# 7segroganti.net
KiCad netlist of a schematic drawn in EAGLE
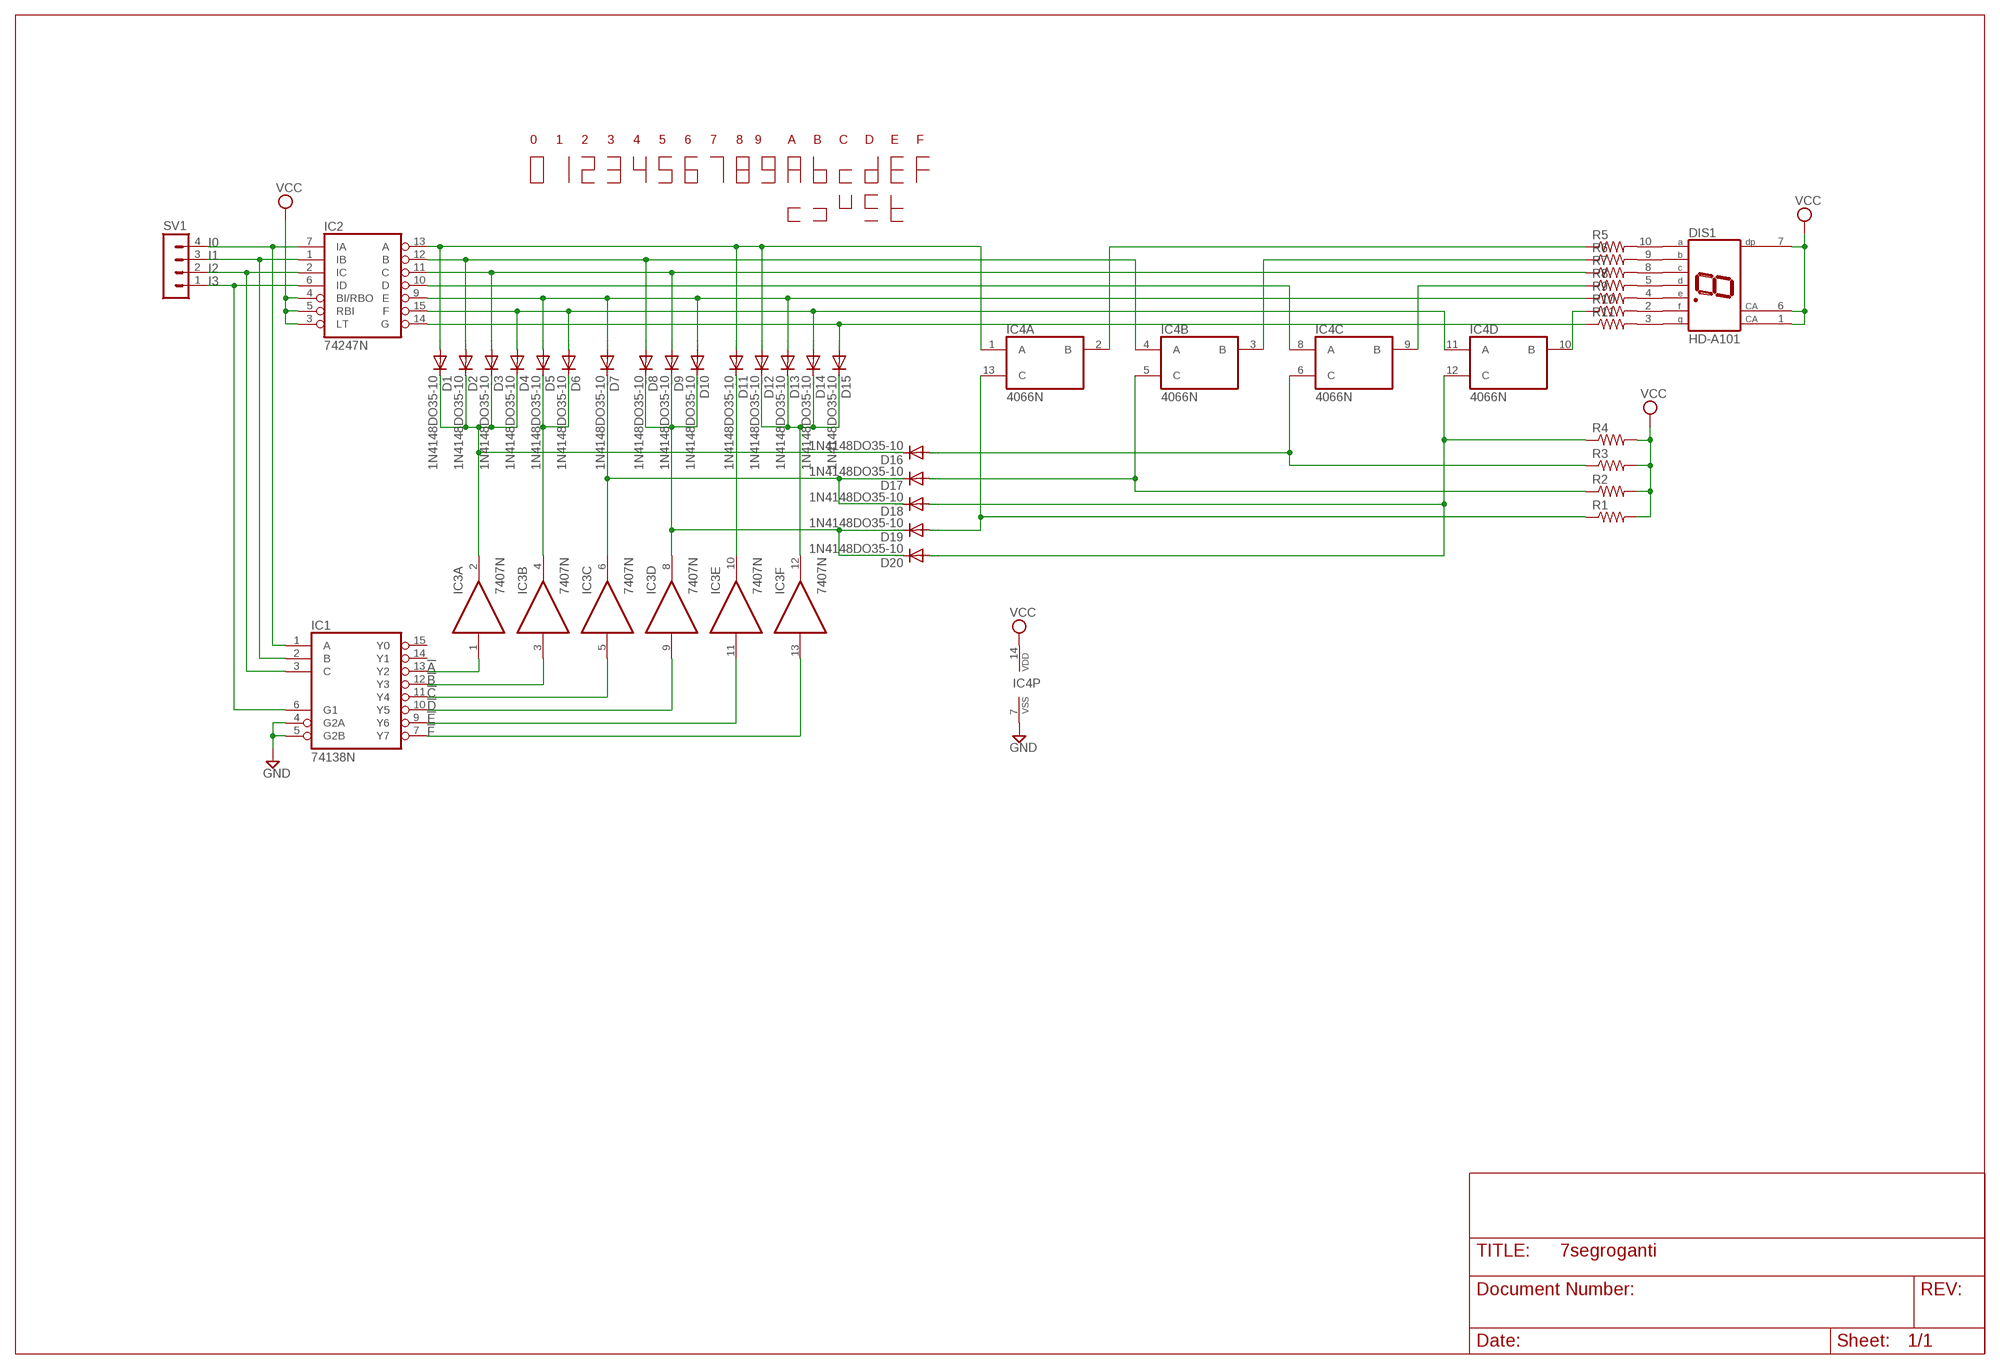
[diagram p0: schematic, sheet 1]

(export (version "E")
  (design (tool "Eeschema 10.0.6"))
  (components
    (comp (ref "D1")
      (value "1N4148DO35-10")
      (footprint "eagle-import:DO35-10")
      (libsource (lib "eagle-import") (part "1N4148DO35-10"))
    )
    (comp (ref "D2")
      (value "1N4148DO35-10")
      (footprint "eagle-import:DO35-10")
      (libsource (lib "eagle-import") (part "1N4148DO35-10"))
    )
    (comp (ref "D3")
      (value "1N4148DO35-10")
      (footprint "eagle-import:DO35-10")
      (libsource (lib "eagle-import") (part "1N4148DO35-10"))
    )
    (comp (ref "D4")
      (value "1N4148DO35-10")
      (footprint "eagle-import:DO35-10")
      (libsource (lib "eagle-import") (part "1N4148DO35-10"))
    )
    (comp (ref "D5")
      (value "1N4148DO35-10")
      (footprint "eagle-import:DO35-10")
      (libsource (lib "eagle-import") (part "1N4148DO35-10"))
    )
    (comp (ref "D6")
      (value "1N4148DO35-10")
      (footprint "eagle-import:DO35-10")
      (libsource (lib "eagle-import") (part "1N4148DO35-10"))
    )
    (comp (ref "D7")
      (value "1N4148DO35-10")
      (footprint "eagle-import:DO35-10")
      (libsource (lib "eagle-import") (part "1N4148DO35-10"))
    )
    (comp (ref "D8")
      (value "1N4148DO35-10")
      (footprint "eagle-import:DO35-10")
      (libsource (lib "eagle-import") (part "1N4148DO35-10"))
    )
    (comp (ref "D9")
      (value "1N4148DO35-10")
      (footprint "eagle-import:DO35-10")
      (libsource (lib "eagle-import") (part "1N4148DO35-10"))
    )
    (comp (ref "D10")
      (value "1N4148DO35-10")
      (footprint "eagle-import:DO35-10")
      (libsource (lib "eagle-import") (part "1N4148DO35-10"))
    )
    (comp (ref "D11")
      (value "1N4148DO35-10")
      (footprint "eagle-import:DO35-10")
      (libsource (lib "eagle-import") (part "1N4148DO35-10"))
    )
    (comp (ref "D12")
      (value "1N4148DO35-10")
      (footprint "eagle-import:DO35-10")
      (libsource (lib "eagle-import") (part "1N4148DO35-10"))
    )
    (comp (ref "D13")
      (value "1N4148DO35-10")
      (footprint "eagle-import:DO35-10")
      (libsource (lib "eagle-import") (part "1N4148DO35-10"))
    )
    (comp (ref "D14")
      (value "1N4148DO35-10")
      (footprint "eagle-import:DO35-10")
      (libsource (lib "eagle-import") (part "1N4148DO35-10"))
    )
    (comp (ref "D15")
      (value "1N4148DO35-10")
      (footprint "eagle-import:DO35-10")
      (libsource (lib "eagle-import") (part "1N4148DO35-10"))
    )
    (comp (ref "D16")
      (value "1N4148DO35-10")
      (footprint "eagle-import:DO35-10")
      (libsource (lib "eagle-import") (part "1N4148DO35-10"))
    )
    (comp (ref "D17")
      (value "1N4148DO35-10")
      (footprint "eagle-import:DO35-10")
      (libsource (lib "eagle-import") (part "1N4148DO35-10"))
    )
    (comp (ref "D18")
      (value "1N4148DO35-10")
      (footprint "eagle-import:DO35-10")
      (libsource (lib "eagle-import") (part "1N4148DO35-10"))
    )
    (comp (ref "D19")
      (value "1N4148DO35-10")
      (footprint "eagle-import:DO35-10")
      (libsource (lib "eagle-import") (part "1N4148DO35-10"))
    )
    (comp (ref "D20")
      (value "1N4148DO35-10")
      (footprint "eagle-import:DO35-10")
      (libsource (lib "eagle-import") (part "1N4148DO35-10"))
    )
    (comp (ref "DIS1")
      (value "HD-A101")
      (footprint "eagle-import:HDSP-A")
      (libsource (lib "eagle-import") (part "HD-A101"))
    )
    (comp (ref "IC1")
      (value "74138N")
      (footprint "eagle-import:DIL16")
      (libsource (lib "eagle-import") (part "74138NS"))
    )
    (comp (ref "IC2")
      (value "74247N")
      (footprint "eagle-import:DIL16")
      (libsource (lib "eagle-import") (part "7446N"))
    )
    (comp (ref "IC3")
      (value "7407N")
      (footprint "eagle-import:DIL14")
      (libsource (lib "eagle-import") (part "7407N"))
    )
    (comp (ref "IC4")
      (value "4066N")
      (footprint "eagle-import:DIL14")
      (libsource (lib "eagle-import") (part "4066N"))
    )
    (comp (ref "R1")
      (value "R-US_0207/10")
      (footprint "eagle-import:0207_10")
      (libsource (lib "eagle-import") (part "R-US_0207/10"))
    )
    (comp (ref "R2")
      (value "R-US_0207/10")
      (footprint "eagle-import:0207_10")
      (libsource (lib "eagle-import") (part "R-US_0207/10"))
    )
    (comp (ref "R3")
      (value "R-US_0207/10")
      (footprint "eagle-import:0207_10")
      (libsource (lib "eagle-import") (part "R-US_0207/10"))
    )
    (comp (ref "R4")
      (value "R-US_0207/10")
      (footprint "eagle-import:0207_10")
      (libsource (lib "eagle-import") (part "R-US_0207/10"))
    )
    (comp (ref "R5")
      (value "R-US_0207/10")
      (footprint "eagle-import:0207_10")
      (libsource (lib "eagle-import") (part "R-US_0207/10"))
    )
    (comp (ref "R6")
      (value "R-US_0207/10")
      (footprint "eagle-import:0207_10")
      (libsource (lib "eagle-import") (part "R-US_0207/10"))
    )
    (comp (ref "R7")
      (value "R-US_0207/10")
      (footprint "eagle-import:0207_10")
      (libsource (lib "eagle-import") (part "R-US_0207/10"))
    )
    (comp (ref "R8")
      (value "R-US_0207/10")
      (footprint "eagle-import:0207_10")
      (libsource (lib "eagle-import") (part "R-US_0207/10"))
    )
    (comp (ref "R9")
      (value "R-US_0207/10")
      (footprint "eagle-import:0207_10")
      (libsource (lib "eagle-import") (part "R-US_0207/10"))
    )
    (comp (ref "R10")
      (value "R-US_0207/10")
      (footprint "eagle-import:0207_10")
      (libsource (lib "eagle-import") (part "R-US_0207/10"))
    )
    (comp (ref "R11")
      (value "R-US_0207/10")
      (footprint "eagle-import:0207_10")
      (libsource (lib "eagle-import") (part "R-US_0207/10"))
    )
    (comp (ref "SV1")
      (value "MA04-1")
      (footprint "eagle-import:MA04-1")
      (libsource (lib "eagle-import") (part "MA04-1"))
    )
  )
  (nets
    (net (code "1") (name "/I0") (class "Default")
      (node (ref "IC1") (pin "1") (pinfunction "A_1") (pintype "input"))
      (node (ref "IC2") (pin "7") (pinfunction "IA_7") (pintype "input"))
      (node (ref "SV1") (pin "4") (pinfunction "4_4") (pintype "passive"))
    )
    (net (code "2") (name "/I1") (class "Default")
      (node (ref "IC1") (pin "2") (pinfunction "B_2") (pintype "input"))
      (node (ref "IC2") (pin "1") (pinfunction "IB_1") (pintype "input"))
      (node (ref "SV1") (pin "3") (pinfunction "3_3") (pintype "passive"))
    )
    (net (code "3") (name "/I2") (class "Default")
      (node (ref "IC1") (pin "3") (pinfunction "C_3") (pintype "input"))
      (node (ref "IC2") (pin "2") (pinfunction "IC_2") (pintype "input"))
      (node (ref "SV1") (pin "2") (pinfunction "2_2") (pintype "passive"))
    )
    (net (code "4") (name "/I3") (class "Default")
      (node (ref "IC1") (pin "6") (pinfunction "G1_6") (pintype "input"))
      (node (ref "IC2") (pin "6") (pinfunction "ID_6") (pintype "input"))
      (node (ref "SV1") (pin "1") (pinfunction "1_1") (pintype "passive"))
    )
    (net (code "5") (name "/~{A}") (class "Default")
      (node (ref "IC1") (pin "13") (pinfunction "Y2_13") (pintype "output"))
      (node (ref "IC3") (pin "1") (pinfunction "I_1") (pintype "input"))
    )
    (net (code "6") (name "/~{B}") (class "Default")
      (node (ref "IC1") (pin "12") (pinfunction "Y3_12") (pintype "output"))
      (node (ref "IC3") (pin "3") (pinfunction "I_3") (pintype "input"))
    )
    (net (code "7") (name "/~{C}") (class "Default")
      (node (ref "IC1") (pin "11") (pinfunction "Y4_11") (pintype "output"))
      (node (ref "IC3") (pin "5") (pinfunction "I_5") (pintype "input"))
    )
    (net (code "8") (name "/~{D}") (class "Default")
      (node (ref "IC1") (pin "10") (pinfunction "Y5_10") (pintype "output"))
      (node (ref "IC3") (pin "9") (pinfunction "I_9") (pintype "input"))
    )
    (net (code "9") (name "/~{E}") (class "Default")
      (node (ref "IC1") (pin "9") (pinfunction "Y6_9") (pintype "output"))
      (node (ref "IC3") (pin "11") (pinfunction "I_11") (pintype "input"))
    )
    (net (code "10") (name "/~{F}") (class "Default")
      (node (ref "IC1") (pin "7") (pinfunction "Y7_7") (pintype "output"))
      (node (ref "IC3") (pin "13") (pinfunction "I_13") (pintype "input"))
    )
    (net (code "11") (name "GND") (class "Default")
      (node (ref "IC1") (pin "4") (pinfunction "G2A_4") (pintype "input"))
      (node (ref "IC1") (pin "5") (pinfunction "G2B_5") (pintype "input"))
      (node (ref "IC4") (pin "7") (pinfunction "VSS_7") (pintype "power_in"))
    )
    (net (code "12") (name "Net-(DIS1-A)") (class "Default")
      (node (ref "DIS1") (pin "10") (pinfunction "A_10") (pintype "passive"))
      (node (ref "R5") (pin "2") (pinfunction "2_2") (pintype "passive"))
    )
    (net (code "13") (name "Net-(DIS1-B)") (class "Default")
      (node (ref "DIS1") (pin "9") (pinfunction "B_9") (pintype "passive"))
      (node (ref "R6") (pin "2") (pinfunction "2_2") (pintype "passive"))
    )
    (net (code "14") (name "Net-(DIS1-C)") (class "Default")
      (node (ref "DIS1") (pin "8") (pinfunction "C_8") (pintype "passive"))
      (node (ref "R7") (pin "2") (pinfunction "2_2") (pintype "passive"))
    )
    (net (code "15") (name "Net-(DIS1-D)") (class "Default")
      (node (ref "DIS1") (pin "5") (pinfunction "D_5") (pintype "passive"))
      (node (ref "R8") (pin "2") (pinfunction "2_2") (pintype "passive"))
    )
    (net (code "16") (name "Net-(DIS1-E)") (class "Default")
      (node (ref "DIS1") (pin "4") (pinfunction "E_4") (pintype "passive"))
      (node (ref "R9") (pin "2") (pinfunction "2_2") (pintype "passive"))
    )
    (net (code "17") (name "Net-(DIS1-F)") (class "Default")
      (node (ref "DIS1") (pin "2") (pinfunction "F_2") (pintype "passive"))
      (node (ref "R10") (pin "2") (pinfunction "2_2") (pintype "passive"))
    )
    (net (code "18") (name "Net-(DIS1-G)") (class "Default")
      (node (ref "DIS1") (pin "3") (pinfunction "G_3") (pintype "passive"))
      (node (ref "R11") (pin "2") (pinfunction "2_2") (pintype "passive"))
    )
    (net (code "19") (name "Net-(IC2A-A)") (class "Default")
      (node (ref "D1") (pin "A") (pinfunction "A_A") (pintype "passive"))
      (node (ref "D11") (pin "A") (pinfunction "A_A") (pintype "passive"))
      (node (ref "D12") (pin "A") (pinfunction "A_A") (pintype "passive"))
      (node (ref "IC2") (pin "13") (pinfunction "A_13") (pintype "open_collector"))
      (node (ref "IC4") (pin "1") (pinfunction "A_1") (pintype "tri_state"))
    )
    (net (code "20") (name "Net-(IC2A-B)") (class "Default")
      (node (ref "D2") (pin "A") (pinfunction "A_A") (pintype "passive"))
      (node (ref "D8") (pin "A") (pinfunction "A_A") (pintype "passive"))
      (node (ref "IC2") (pin "12") (pinfunction "B_12") (pintype "open_collector"))
      (node (ref "IC4") (pin "4") (pinfunction "A_4") (pintype "tri_state"))
    )
    (net (code "21") (name "Net-(IC2A-C)") (class "Default")
      (node (ref "D3") (pin "A") (pinfunction "A_A") (pintype "passive"))
      (node (ref "D9") (pin "A") (pinfunction "A_A") (pintype "passive"))
      (node (ref "IC2") (pin "11") (pinfunction "C_11") (pintype "open_collector"))
      (node (ref "R7") (pin "1") (pinfunction "1_1") (pintype "passive"))
    )
    (net (code "22") (name "Net-(IC2A-D)") (class "Default")
      (node (ref "IC2") (pin "10") (pinfunction "D_10") (pintype "open_collector"))
      (node (ref "IC4") (pin "8") (pinfunction "A_8") (pintype "tri_state"))
    )
    (net (code "23") (name "Net-(IC2A-E)") (class "Default")
      (node (ref "D10") (pin "A") (pinfunction "A_A") (pintype "passive"))
      (node (ref "D13") (pin "A") (pinfunction "A_A") (pintype "passive"))
      (node (ref "D5") (pin "A") (pinfunction "A_A") (pintype "passive"))
      (node (ref "D7") (pin "A") (pinfunction "A_A") (pintype "passive"))
      (node (ref "IC2") (pin "9") (pinfunction "E_9") (pintype "open_collector"))
      (node (ref "R9") (pin "1") (pinfunction "1_1") (pintype "passive"))
    )
    (net (code "24") (name "Net-(IC2A-F)") (class "Default")
      (node (ref "D14") (pin "A") (pinfunction "A_A") (pintype "passive"))
      (node (ref "D4") (pin "A") (pinfunction "A_A") (pintype "passive"))
      (node (ref "D6") (pin "A") (pinfunction "A_A") (pintype "passive"))
      (node (ref "IC2") (pin "15") (pinfunction "F_15") (pintype "open_collector"))
      (node (ref "IC4") (pin "11") (pinfunction "A_11") (pintype "tri_state"))
    )
    (net (code "25") (name "Net-(IC2A-G)") (class "Default")
      (node (ref "D15") (pin "A") (pinfunction "A_A") (pintype "passive"))
      (node (ref "IC2") (pin "14") (pinfunction "G_14") (pintype "open_collector"))
      (node (ref "R11") (pin "1") (pinfunction "1_1") (pintype "passive"))
    )
    (net (code "26") (name "Net-(IC3A-O)") (class "Default")
      (node (ref "D1") (pin "C") (pinfunction "C_C") (pintype "passive"))
      (node (ref "D16") (pin "C") (pinfunction "C_C") (pintype "passive"))
      (node (ref "D2") (pin "C") (pinfunction "C_C") (pintype "passive"))
      (node (ref "D3") (pin "C") (pinfunction "C_C") (pintype "passive"))
      (node (ref "D4") (pin "C") (pinfunction "C_C") (pintype "passive"))
      (node (ref "IC3") (pin "2") (pinfunction "O_2") (pintype "open_collector"))
    )
    (net (code "27") (name "Net-(IC3B-O)") (class "Default")
      (node (ref "D5") (pin "C") (pinfunction "C_C") (pintype "passive"))
      (node (ref "D6") (pin "C") (pinfunction "C_C") (pintype "passive"))
      (node (ref "IC3") (pin "4") (pinfunction "O_4") (pintype "open_collector"))
    )
    (net (code "28") (name "Net-(IC3C-O)") (class "Default")
      (node (ref "D17") (pin "C") (pinfunction "C_C") (pintype "passive"))
      (node (ref "D18") (pin "C") (pinfunction "C_C") (pintype "passive"))
      (node (ref "D7") (pin "C") (pinfunction "C_C") (pintype "passive"))
      (node (ref "IC3") (pin "6") (pinfunction "O_6") (pintype "open_collector"))
    )
    (net (code "29") (name "Net-(IC3D-O)") (class "Default")
      (node (ref "D10") (pin "C") (pinfunction "C_C") (pintype "passive"))
      (node (ref "D19") (pin "C") (pinfunction "C_C") (pintype "passive"))
      (node (ref "D20") (pin "C") (pinfunction "C_C") (pintype "passive"))
      (node (ref "D8") (pin "C") (pinfunction "C_C") (pintype "passive"))
      (node (ref "D9") (pin "C") (pinfunction "C_C") (pintype "passive"))
      (node (ref "IC3") (pin "8") (pinfunction "O_8") (pintype "open_collector"))
    )
    (net (code "30") (name "Net-(IC3E-O)") (class "Default")
      (node (ref "D11") (pin "C") (pinfunction "C_C") (pintype "passive"))
      (node (ref "IC3") (pin "10") (pinfunction "O_10") (pintype "open_collector"))
    )
    (net (code "31") (name "Net-(IC3F-O)") (class "Default")
      (node (ref "D12") (pin "C") (pinfunction "C_C") (pintype "passive"))
      (node (ref "D13") (pin "C") (pinfunction "C_C") (pintype "passive"))
      (node (ref "D14") (pin "C") (pinfunction "C_C") (pintype "passive"))
      (node (ref "D15") (pin "C") (pinfunction "C_C") (pintype "passive"))
      (node (ref "IC3") (pin "12") (pinfunction "O_12") (pintype "open_collector"))
    )
    (net (code "32") (name "Net-(IC4A-B)") (class "Default")
      (node (ref "IC4") (pin "2") (pinfunction "B_2") (pintype "tri_state"))
      (node (ref "R5") (pin "1") (pinfunction "1_1") (pintype "passive"))
    )
    (net (code "33") (name "Net-(IC4A-C)") (class "Default")
      (node (ref "D19") (pin "A") (pinfunction "A_A") (pintype "passive"))
      (node (ref "IC4") (pin "13") (pinfunction "C_13") (pintype "input"))
      (node (ref "R1") (pin "1") (pinfunction "1_1") (pintype "passive"))
    )
    (net (code "34") (name "Net-(IC4B-B)") (class "Default")
      (node (ref "IC4") (pin "3") (pinfunction "B_3") (pintype "tri_state"))
      (node (ref "R6") (pin "1") (pinfunction "1_1") (pintype "passive"))
    )
    (net (code "35") (name "Net-(IC4B-C)") (class "Default")
      (node (ref "D17") (pin "A") (pinfunction "A_A") (pintype "passive"))
      (node (ref "IC4") (pin "5") (pinfunction "C_5") (pintype "input"))
      (node (ref "R2") (pin "1") (pinfunction "1_1") (pintype "passive"))
    )
    (net (code "36") (name "Net-(IC4C-B)") (class "Default")
      (node (ref "IC4") (pin "9") (pinfunction "B_9") (pintype "tri_state"))
      (node (ref "R8") (pin "1") (pinfunction "1_1") (pintype "passive"))
    )
    (net (code "37") (name "Net-(IC4C-C)") (class "Default")
      (node (ref "D16") (pin "A") (pinfunction "A_A") (pintype "passive"))
      (node (ref "IC4") (pin "6") (pinfunction "C_6") (pintype "input"))
      (node (ref "R3") (pin "1") (pinfunction "1_1") (pintype "passive"))
    )
    (net (code "38") (name "Net-(IC4D-B)") (class "Default")
      (node (ref "IC4") (pin "10") (pinfunction "B_10") (pintype "tri_state"))
      (node (ref "R10") (pin "1") (pinfunction "1_1") (pintype "passive"))
    )
    (net (code "39") (name "Net-(IC4D-C)") (class "Default")
      (node (ref "D18") (pin "A") (pinfunction "A_A") (pintype "passive"))
      (node (ref "D20") (pin "A") (pinfunction "A_A") (pintype "passive"))
      (node (ref "IC4") (pin "12") (pinfunction "C_12") (pintype "input"))
      (node (ref "R4") (pin "1") (pinfunction "1_1") (pintype "passive"))
    )
    (net (code "40") (name "VCC") (class "Default")
      (node (ref "DIS1") (pin "1") (pinfunction "CA_1") (pintype "passive"))
      (node (ref "DIS1") (pin "6") (pinfunction "CA_6") (pintype "passive"))
      (node (ref "DIS1") (pin "7") (pinfunction "DP_7") (pintype "passive"))
      (node (ref "IC2") (pin "3") (pinfunction "LT_3") (pintype "input"))
      (node (ref "IC2") (pin "4") (pinfunction "BI/RBO_4") (pintype "input"))
      (node (ref "IC2") (pin "5") (pinfunction "RBI_5") (pintype "input"))
      (node (ref "IC4") (pin "14") (pinfunction "VDD_14") (pintype "power_in"))
      (node (ref "R1") (pin "2") (pinfunction "2_2") (pintype "passive"))
      (node (ref "R2") (pin "2") (pinfunction "2_2") (pintype "passive"))
      (node (ref "R3") (pin "2") (pinfunction "2_2") (pintype "passive"))
      (node (ref "R4") (pin "2") (pinfunction "2_2") (pintype "passive"))
    )
    (net (code "41") (name "unconnected-(IC1A-Y0-Pad15)") (class "Default")
      (node (ref "IC1") (pin "15") (pinfunction "Y0_15") (pintype "output"))
    )
    (net (code "42") (name "unconnected-(IC1A-Y1-Pad14)") (class "Default")
      (node (ref "IC1") (pin "14") (pinfunction "Y1_14") (pintype "output"))
    )
  )
)
